# NEO-M9N.net
KiCad netlist of a schematic drawn in Altium Designer
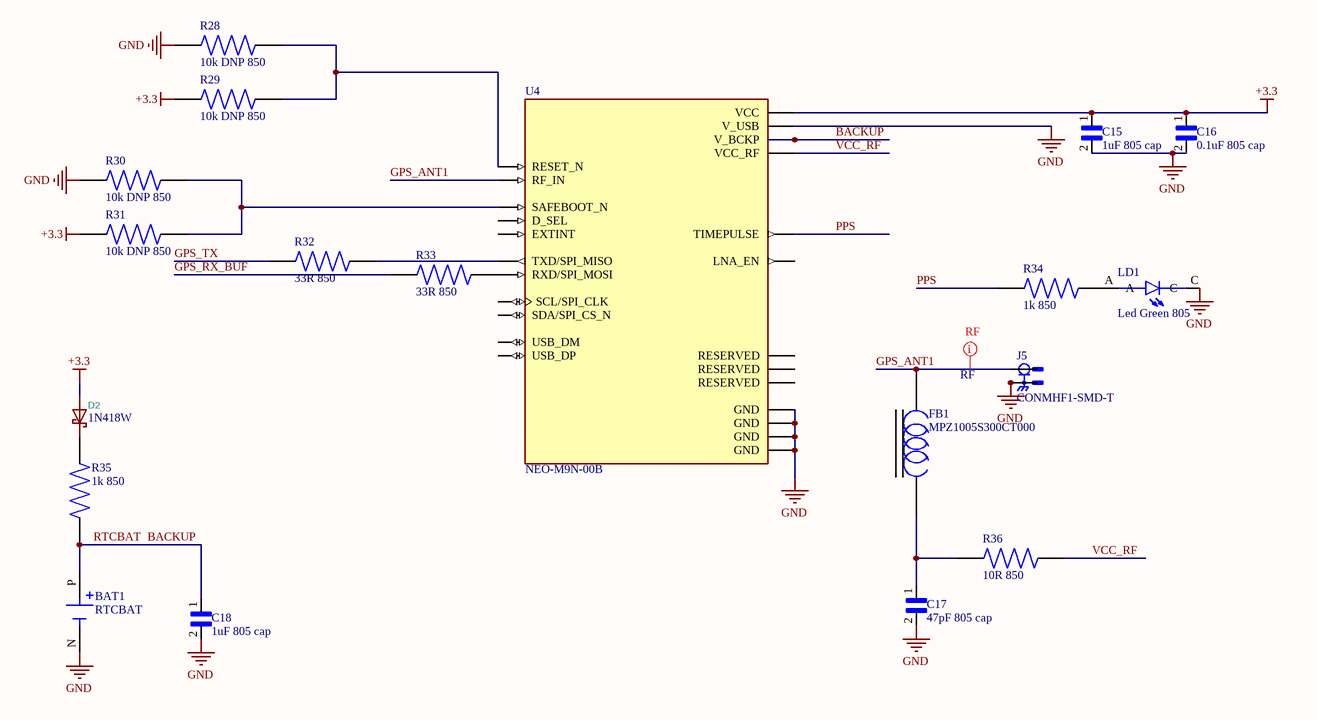
[diagram p0: NEO-M9N.SchDoc]

(export (version "E")
  (design (tool "Eeschema 10.0.6"))
  (components
    (comp (ref "BAT1")
      (value "RTCBAT")
      (footprint "RTCBATTERY")
      (libsource (lib "iee_altium") (part "RTCBAT"))
    )
    (comp (ref "C15")
      (value "1uF 805 cap")
      (footprint "1uF 805 Cap")
      (libsource (lib "iee_altium") (part "1uF 805 cap"))
    )
    (comp (ref "C16")
      (value "0.1uF 805 cap")
      (footprint "1uF 805 Cap")
      (libsource (lib "iee_altium") (part "1uF 805 cap"))
    )
    (comp (ref "C17")
      (value "47pF 805 cap")
      (footprint "1uF 805 Cap")
      (libsource (lib "iee_altium") (part "1uF 805 cap"))
    )
    (comp (ref "C18")
      (value "1uF 805 cap")
      (footprint "1uF 805 Cap")
      (libsource (lib "iee_altium") (part "1uF 805 cap"))
    )
    (comp (ref "D2") (value "1N418W") (footprint "SOD-523") (libsource (lib "iee_altium") (part "1N418W")))
    (comp (ref "FB1")
      (value "MPZ1005S300CT000")
      (footprint "BEADC1005X50N")
      (libsource (lib "iee_altium") (part "MPZ1005S300CT000"))
    )
    (comp (ref "J5")
      (value "CONMHF1-SMD-T")
      (footprint "TE_CONMHF1-SMD-T")
      (libsource (lib "iee_altium") (part "CONMHF1-SMD-T"))
    )
    (comp (ref "LD1")
      (value "Led Green 805")
      (footprint "Led Green 805")
      (libsource (lib "iee_altium") (part "Led Green 805"))
    )
    (comp (ref "R28")
      (value "10k DNP 850")
      (footprint "10k 850")
      (libsource (lib "iee_altium") (part "10k 850"))
    )
    (comp (ref "R29")
      (value "10k DNP 850")
      (footprint "10k 850")
      (libsource (lib "iee_altium") (part "10k 850"))
    )
    (comp (ref "R30")
      (value "10k DNP 850")
      (footprint "10k 850")
      (libsource (lib "iee_altium") (part "10k 850"))
    )
    (comp (ref "R31")
      (value "10k DNP 850")
      (footprint "10k 850")
      (libsource (lib "iee_altium") (part "10k 850"))
    )
    (comp (ref "R32") (value "33R 850") (footprint "10k 850") (libsource (lib "iee_altium") (part "10k 850")))
    (comp (ref "R33") (value "33R 850") (footprint "10k 850") (libsource (lib "iee_altium") (part "10k 850")))
    (comp (ref "R34") (value "1k 850") (footprint "10k 850") (libsource (lib "iee_altium") (part "10k 850")))
    (comp (ref "R35") (value "1k 850") (footprint "10k 850") (libsource (lib "iee_altium") (part "10k 850")))
    (comp (ref "R36") (value "10R 850") (footprint "10k 850") (libsource (lib "iee_altium") (part "10k 850")))
    (comp (ref "U4")
      (value "NEO-M9N-00B")
      (footprint "XCVR_NEO-M9N-00B")
      (description "series RF Receiver BeiDou, Galileo, GLONASS, GNSS, GPS - -167dBm - - Module")
      (fields (field (name "MF") "u-blox"))
      (libsource (lib "iee_altium") (part "NEO-M9N-00B"))
    )
  )
  (nets
    (net (code "1") (name "+3.3") (class "Default")
      (node (ref "C15") (pin "1") (pinfunction "1_1") (pintype "passive"))
      (node (ref "C16") (pin "1") (pinfunction "1_1") (pintype "passive"))
      (node (ref "D2") (pin "A") (pinfunction "A_A") (pintype "passive"))
      (node (ref "R29") (pin "1") (pinfunction "1_1") (pintype "passive"))
      (node (ref "R31") (pin "1") (pinfunction "1_1") (pintype "passive"))
      (node (ref "U4") (pin "23") (pinfunction "VCC_23") (pintype "power_in"))
    )
    (net (code "2") (name "/BACKUP") (class "Default")
      (node (ref "BAT1") (pin "P") (pinfunction "POS_P") (pintype "passive"))
      (node (ref "C18") (pin "1") (pinfunction "1_1") (pintype "passive"))
      (node (ref "R35") (pin "2") (pinfunction "2_2") (pintype "passive"))
      (node (ref "U4") (pin "22") (pinfunction "V_BCKP_22") (pintype "power_in"))
    )
    (net (code "3") (name "/GPS_ANT1") (class "Default")
      (node (ref "FB1") (pin "1") (pinfunction "1_1") (pintype "passive"))
      (node (ref "J5") (pin "1") (pinfunction "SIG_1") (pintype "passive"))
      (node (ref "U4") (pin "11") (pinfunction "RF_IN_11") (pintype "input"))
    )
    (net (code "4") (name "/GPS_RX_BUF") (class "Default")
      (node (ref "R33") (pin "1") (pinfunction "1_1") (pintype "passive"))
    )
    (net (code "5") (name "/GPS_TX") (class "Default")
      (node (ref "R32") (pin "1") (pinfunction "1_1") (pintype "passive"))
    )
    (net (code "6") (name "/PPS") (class "Default")
      (node (ref "R34") (pin "1") (pinfunction "1_1") (pintype "passive"))
      (node (ref "U4") (pin "3") (pinfunction "TIMEPULSE_3") (pintype "output"))
    )
    (net (code "7") (name "/VCC_RF") (class "Default")
      (node (ref "R36") (pin "2") (pinfunction "2_2") (pintype "passive"))
      (node (ref "U4") (pin "9") (pinfunction "VCC_RF_9") (pintype "power_in"))
    )
    (net (code "8") (name "GND") (class "Default")
      (node (ref "BAT1") (pin "N") (pinfunction "NEG_N") (pintype "passive"))
      (node (ref "C15") (pin "2") (pinfunction "2_2") (pintype "passive"))
      (node (ref "C16") (pin "2") (pinfunction "2_2") (pintype "passive"))
      (node (ref "C17") (pin "2") (pinfunction "2_2") (pintype "passive"))
      (node (ref "C18") (pin "2") (pinfunction "2_2") (pintype "passive"))
      (node (ref "J5") (pin "2") (pinfunction "GND_2") (pintype "power_in"))
      (node (ref "J5") (pin "3") (pinfunction "GND_3") (pintype "power_in"))
      (node (ref "J5") (pin "4") (pinfunction "GND_4") (pintype "power_in"))
      (node (ref "LD1") (pin "C") (pinfunction "C_C") (pintype "passive"))
      (node (ref "R28") (pin "1") (pinfunction "1_1") (pintype "passive"))
      (node (ref "R30") (pin "1") (pinfunction "1_1") (pintype "passive"))
      (node (ref "U4") (pin "10") (pinfunction "GND_10") (pintype "power_in"))
      (node (ref "U4") (pin "12") (pinfunction "GND_12") (pintype "power_in"))
      (node (ref "U4") (pin "13") (pinfunction "GND_13") (pintype "power_in"))
      (node (ref "U4") (pin "24") (pinfunction "GND_24") (pintype "power_in"))
      (node (ref "U4") (pin "7") (pinfunction "V_USB_7") (pintype "power_in"))
    )
    (net (code "9") (name "Net-(C17-Pad1)") (class "Default")
      (node (ref "C17") (pin "1") (pinfunction "1_1") (pintype "passive"))
      (node (ref "FB1") (pin "2") (pinfunction "2_2") (pintype "passive"))
      (node (ref "R36") (pin "1") (pinfunction "1_1") (pintype "passive"))
    )
    (net (code "10") (name "Net-(D2-PadK)") (class "Default")
      (node (ref "D2") (pin "K") (pinfunction "K_K") (pintype "passive"))
      (node (ref "R35") (pin "1") (pinfunction "1_1") (pintype "passive"))
    )
    (net (code "11") (name "Net-(LD1-PadA)") (class "Default")
      (node (ref "LD1") (pin "A") (pinfunction "A_A") (pintype "passive"))
      (node (ref "R34") (pin "2") (pinfunction "2_2") (pintype "passive"))
    )
    (net (code "12") (name "Net-(U4-RESET_N)") (class "Default")
      (node (ref "R28") (pin "2") (pinfunction "2_2") (pintype "passive"))
      (node (ref "R29") (pin "2") (pinfunction "2_2") (pintype "passive"))
      (node (ref "U4") (pin "8") (pinfunction "RESET_N_8") (pintype "input"))
    )
    (net (code "13") (name "Net-(U4-RXD{slash}SPI_MOSI)") (class "Default")
      (node (ref "R33") (pin "2") (pinfunction "2_2") (pintype "passive"))
      (node (ref "U4") (pin "21") (pinfunction "RXD/SPI_MOSI_21") (pintype "input"))
    )
    (net (code "14") (name "Net-(U4-SAFEBOOT_N)") (class "Default")
      (node (ref "R30") (pin "2") (pinfunction "2_2") (pintype "passive"))
      (node (ref "R31") (pin "2") (pinfunction "2_2") (pintype "passive"))
      (node (ref "U4") (pin "1") (pinfunction "SAFEBOOT_N_1") (pintype "input"))
    )
    (net (code "15") (name "Net-(U4-TXD{slash}SPI_MISO)") (class "Default")
      (node (ref "R32") (pin "2") (pinfunction "2_2") (pintype "passive"))
      (node (ref "U4") (pin "20") (pinfunction "TXD/SPI_MISO_20") (pintype "output"))
    )
    (net (code "16") (name "unconnected-(U4-D_SEL-Pad2)") (class "Default")
      (node (ref "U4") (pin "2") (pinfunction "D_SEL_2") (pintype "input"))
    )
    (net (code "17") (name "unconnected-(U4-EXTINT-Pad4)") (class "Default")
      (node (ref "U4") (pin "4") (pinfunction "EXTINT_4") (pintype "input"))
    )
    (net (code "18") (name "unconnected-(U4-LNA_EN-Pad14)") (class "Default")
      (node (ref "U4") (pin "14") (pinfunction "LNA_EN_14") (pintype "output"))
    )
    (net (code "19") (name "unconnected-(U4-RESERVED-Pad15)") (class "Default")
      (node (ref "U4") (pin "15") (pinfunction "RESERVED_15") (pintype "passive"))
    )
    (net (code "20") (name "unconnected-(U4-RESERVED-Pad16)") (class "Default")
      (node (ref "U4") (pin "16") (pinfunction "RESERVED_16") (pintype "passive"))
    )
    (net (code "21") (name "unconnected-(U4-RESERVED-Pad17)") (class "Default")
      (node (ref "U4") (pin "17") (pinfunction "RESERVED_17") (pintype "passive"))
    )
    (net (code "22") (name "unconnected-(U4-SCL{slash}SPI_CLK-Pad19)") (class "Default")
      (node (ref "U4") (pin "19") (pinfunction "SCL/SPI_CLK_19") (pintype "bidirectional"))
    )
    (net (code "23") (name "unconnected-(U4-SDA{slash}SPI_CS_N-Pad18)") (class "Default")
      (node (ref "U4") (pin "18") (pinfunction "SDA/SPI_CS_N_18") (pintype "bidirectional"))
    )
    (net (code "24") (name "unconnected-(U4-USB_DM-Pad5)") (class "Default")
      (node (ref "U4") (pin "5") (pinfunction "USB_DM_5") (pintype "bidirectional"))
    )
    (net (code "25") (name "unconnected-(U4-USB_DP-Pad6)") (class "Default")
      (node (ref "U4") (pin "6") (pinfunction "USB_DP_6") (pintype "bidirectional"))
    )
  )
)
